# usb.net
KiCad netlist of a schematic drawn in Altium Designer
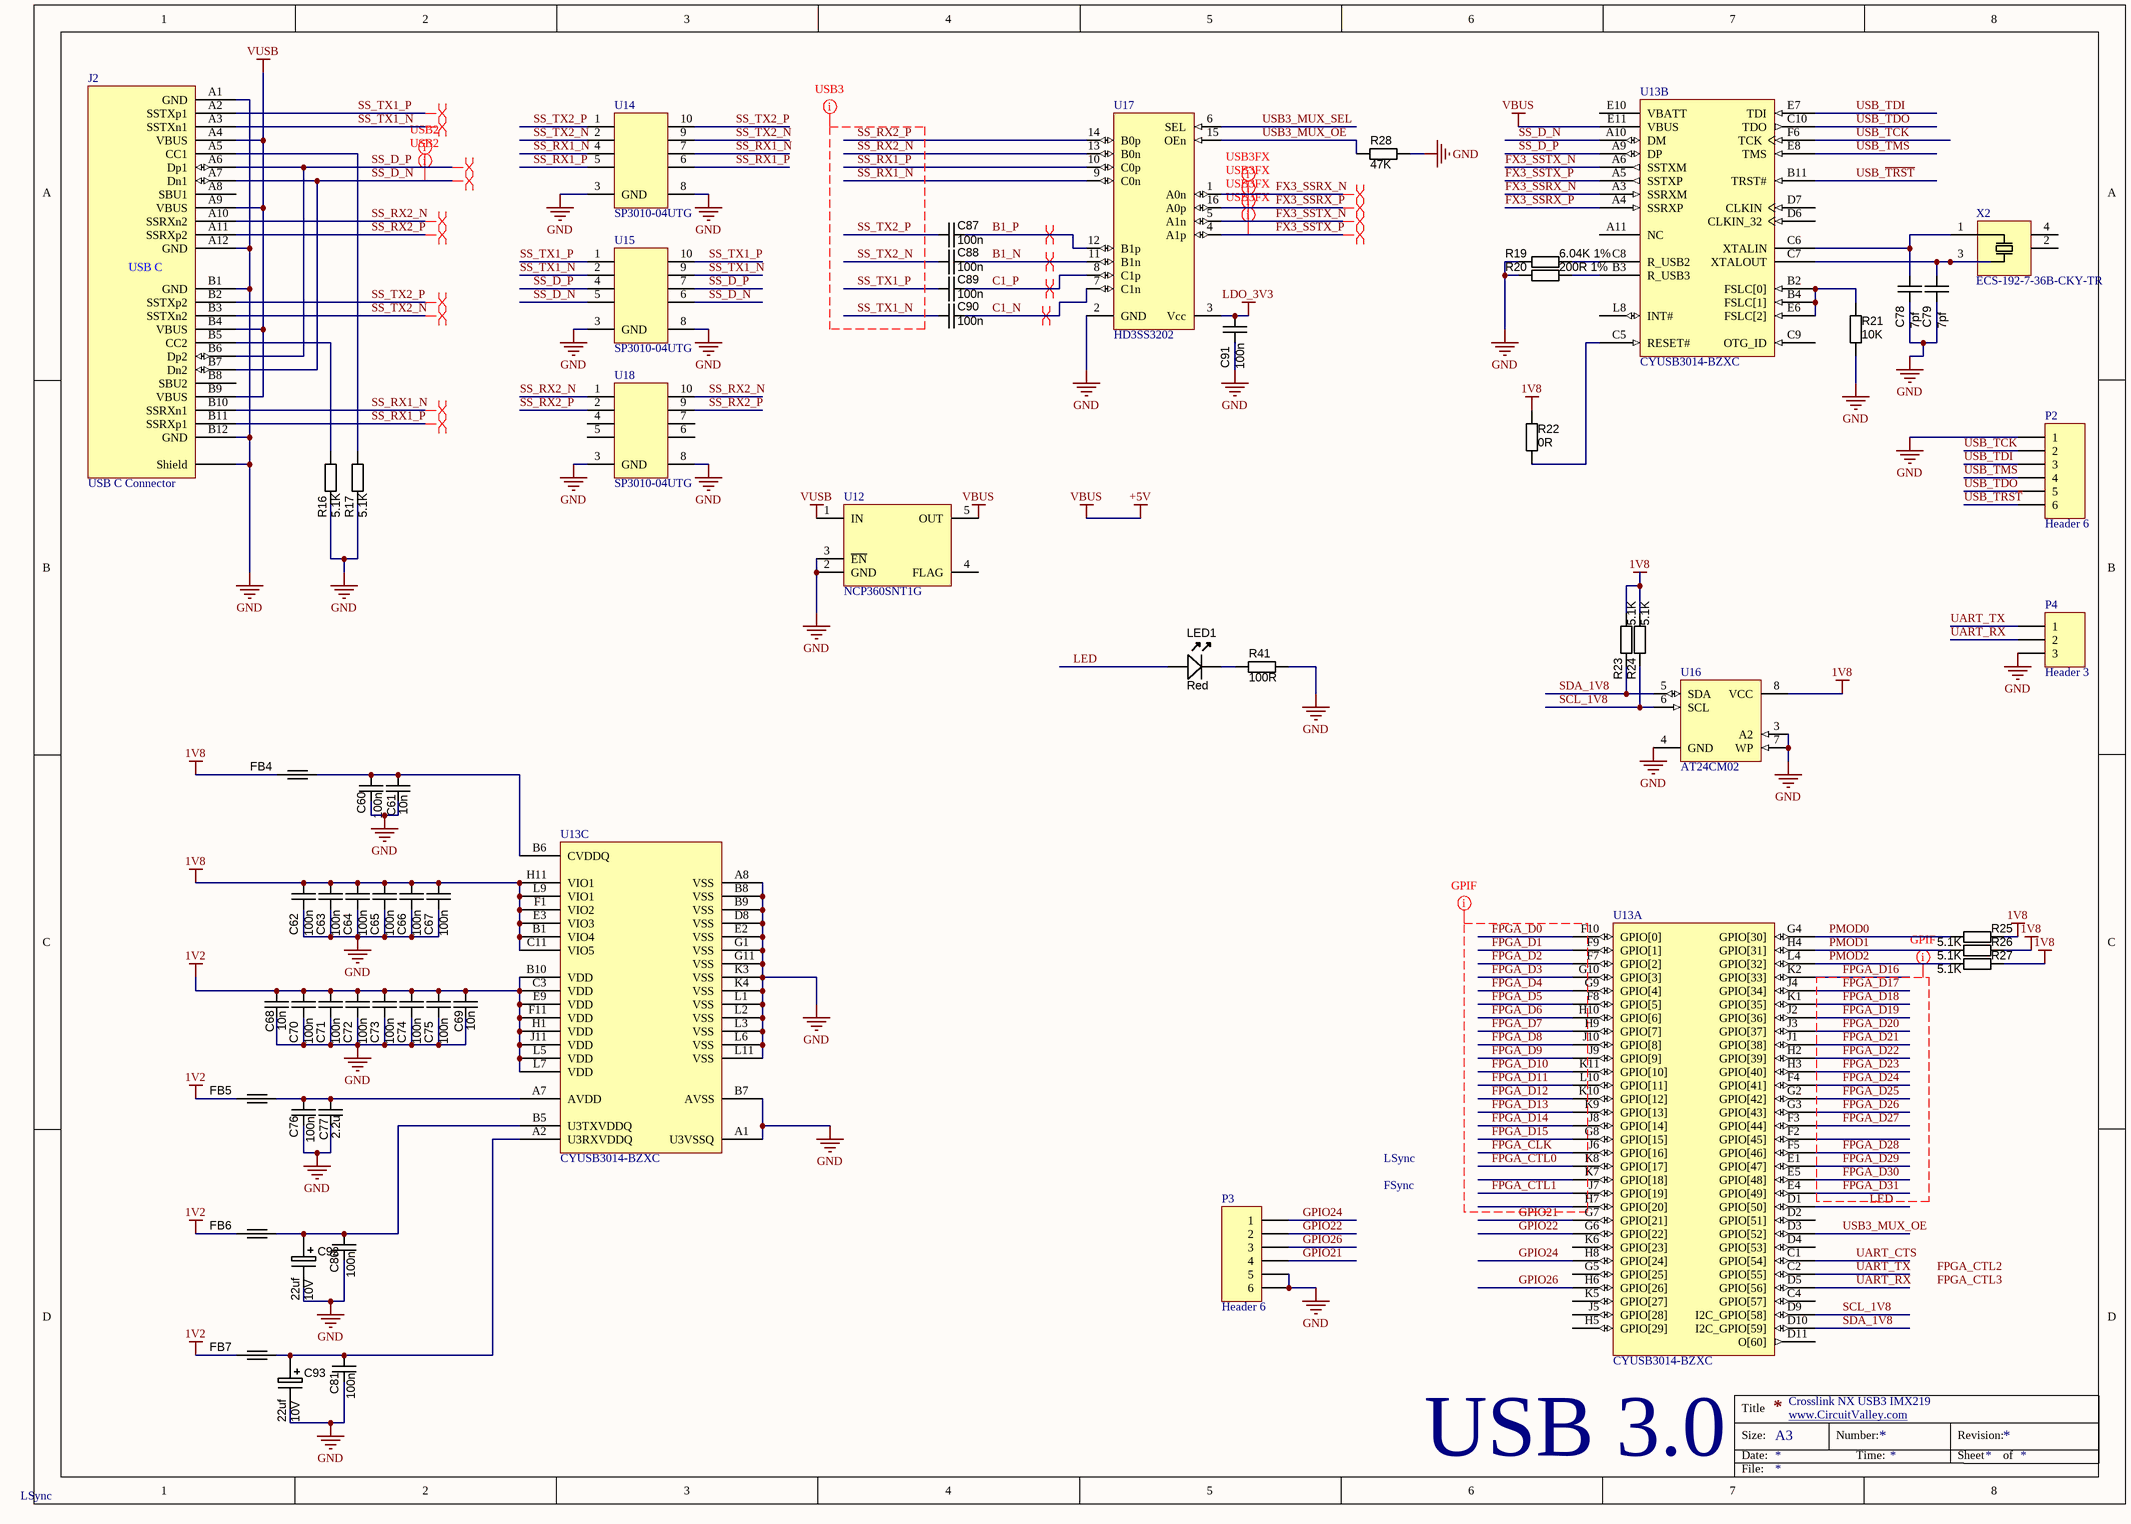
[diagram p0: usb.SchDoc]

(export (version "E")
  (design (tool "Eeschema 10.0.6"))
  (components
    (comp (ref "C60")
      (value "100n")
      (footprint "CAPC1608N")
      (description "Capacitor SMD Cer 10pF 5% 50V NP0 0603")
      (fields (field (name "TOLERANCE") "±5%") (field (name "PART") "C0603X104K5RAC"))
      (libsource (lib "PBL - Capacitors") (part "CAPC_10p_0603_NP0_1%_50V"))
    )
    (comp (ref "C61")
      (value "10n")
      (footprint "CAPC1608N")
      (description "Capacitor SMD Cer 10pF 5% 50V NP0 0603")
      (fields (field (name "TOLERANCE") "±5%") (field (name "PART") "C0603X104K5RAC"))
      (libsource (lib "PBL - Capacitors") (part "CAPC_10p_0603_NP0_1%_50V"))
    )
    (comp (ref "C62")
      (value "100n")
      (footprint "CAPC1608N")
      (description "Capacitor SMD Cer 10pF 5% 50V NP0 0603")
      (fields (field (name "TOLERANCE") "±5%") (field (name "PART") "C0603X104K5RAC"))
      (libsource (lib "PBL - Capacitors") (part "CAPC_10p_0603_NP0_1%_50V"))
    )
    (comp (ref "C63")
      (value "100n")
      (footprint "CAPC1608N")
      (description "Capacitor SMD Cer 10pF 5% 50V NP0 0603")
      (fields (field (name "TOLERANCE") "±5%") (field (name "PART") "C0603X104K5RAC"))
      (libsource (lib "PBL - Capacitors") (part "CAPC_10p_0603_NP0_1%_50V"))
    )
    (comp (ref "C64")
      (value "100n")
      (footprint "CAPC1608N")
      (description "Capacitor SMD Cer 10pF 5% 50V NP0 0603")
      (fields (field (name "TOLERANCE") "±5%") (field (name "PART") "C0603X104K5RAC"))
      (libsource (lib "PBL - Capacitors") (part "CAPC_10p_0603_NP0_1%_50V"))
    )
    (comp (ref "C65")
      (value "100n")
      (footprint "CAPC1608N")
      (description "Capacitor SMD Cer 10pF 5% 50V NP0 0603")
      (fields (field (name "TOLERANCE") "±5%") (field (name "PART") "C0603X104K5RAC"))
      (libsource (lib "PBL - Capacitors") (part "CAPC_10p_0603_NP0_1%_50V"))
    )
    (comp (ref "C66")
      (value "100n")
      (footprint "CAPC1608N")
      (description "Capacitor SMD Cer 10pF 5% 50V NP0 0603")
      (fields (field (name "TOLERANCE") "±5%") (field (name "PART") "C0603X104K5RAC"))
      (libsource (lib "PBL - Capacitors") (part "CAPC_10p_0603_NP0_1%_50V"))
    )
    (comp (ref "C67")
      (value "100n")
      (footprint "CAPC1608N")
      (description "Capacitor SMD Cer 10pF 5% 50V NP0 0603")
      (fields (field (name "TOLERANCE") "±5%") (field (name "PART") "C0603X104K5RAC"))
      (libsource (lib "PBL - Capacitors") (part "CAPC_10p_0603_NP0_1%_50V"))
    )
    (comp (ref "C68")
      (value "10n")
      (footprint "CAPC1608N")
      (description "Capacitor SMD Cer 10pF 5% 50V NP0 0603")
      (fields (field (name "TOLERANCE") "±5%") (field (name "PART") "C0603X104K5RAC"))
      (libsource (lib "PBL - Capacitors") (part "CAPC_10p_0603_NP0_1%_50V"))
    )
    (comp (ref "C69")
      (value "10n")
      (footprint "CAPC1608N")
      (description "Capacitor SMD Cer 10pF 5% 50V NP0 0603")
      (fields (field (name "TOLERANCE") "±5%") (field (name "PART") "C0603X104K5RAC"))
      (libsource (lib "PBL - Capacitors") (part "CAPC_10p_0603_NP0_1%_50V"))
    )
    (comp (ref "C70")
      (value "100n")
      (footprint "CAPC1608N")
      (description "Capacitor SMD Cer 10pF 5% 50V NP0 0603")
      (fields (field (name "TOLERANCE") "±5%") (field (name "PART") "C0603X104K5RAC"))
      (libsource (lib "PBL - Capacitors") (part "CAPC_10p_0603_NP0_1%_50V"))
    )
    (comp (ref "C71")
      (value "100n")
      (footprint "CAPC1608N")
      (description "Capacitor SMD Cer 10pF 5% 50V NP0 0603")
      (fields (field (name "TOLERANCE") "±5%") (field (name "PART") "C0603X104K5RAC"))
      (libsource (lib "PBL - Capacitors") (part "CAPC_10p_0603_NP0_1%_50V"))
    )
    (comp (ref "C72")
      (value "100n")
      (footprint "CAPC1608N")
      (description "Capacitor SMD Cer 10pF 5% 50V NP0 0603")
      (fields (field (name "TOLERANCE") "±5%") (field (name "PART") "C0603X104K5RAC"))
      (libsource (lib "PBL - Capacitors") (part "CAPC_10p_0603_NP0_1%_50V"))
    )
    (comp (ref "C73")
      (value "100n")
      (footprint "CAPC1608N")
      (description "Capacitor SMD Cer 10pF 5% 50V NP0 0603")
      (fields (field (name "TOLERANCE") "±5%") (field (name "PART") "C0603X104K5RAC"))
      (libsource (lib "PBL - Capacitors") (part "CAPC_10p_0603_NP0_1%_50V"))
    )
    (comp (ref "C74")
      (value "100n")
      (footprint "CAPC1608N")
      (description "Capacitor SMD Cer 10pF 5% 50V NP0 0603")
      (fields (field (name "TOLERANCE") "±5%") (field (name "PART") "C0603X104K5RAC"))
      (libsource (lib "PBL - Capacitors") (part "CAPC_10p_0603_NP0_1%_50V"))
    )
    (comp (ref "C75")
      (value "100n")
      (footprint "CAPC1608N")
      (description "Capacitor SMD Cer 10pF 5% 50V NP0 0603")
      (fields (field (name "TOLERANCE") "±5%") (field (name "PART") "C0603X104K5RAC"))
      (libsource (lib "PBL - Capacitors") (part "CAPC_10p_0603_NP0_1%_50V"))
    )
    (comp (ref "C76")
      (value "100n")
      (footprint "CAPC1608N")
      (description "Capacitor SMD Cer 10pF 5% 50V NP0 0603")
      (fields (field (name "TOLERANCE") "±5%") (field (name "PART") "C0603X104K5RAC"))
      (libsource (lib "PBL - Capacitors") (part "CAPC_10p_0603_NP0_1%_50V"))
    )
    (comp (ref "C77")
      (value "2.2u")
      (footprint "CAPC1608N")
      (description "Capacitor SMD Cer 10pF 5% 50V NP0 0603")
      (fields (field (name "TOLERANCE") "±5%") (field (name "PART") "C0603X104K5RAC"))
      (libsource (lib "PBL - Capacitors") (part "CAPC_10p_0603_NP0_1%_50V"))
    )
    (comp (ref "C78")
      (value "7pf")
      (footprint "CAPC1608N")
      (description "Capacitor SMD Cer 10pF 5% 50V NP0 0603")
      (fields (field (name "TOLERANCE") "±5%") (field (name "PART") "C0603X104K5RAC"))
      (libsource (lib "PBL - Capacitors") (part "CAPC_10p_0603_NP0_1%_50V"))
    )
    (comp (ref "C79")
      (value "7pf")
      (footprint "CAPC1608N")
      (description "Capacitor SMD Cer 10pF 5% 50V NP0 0603")
      (fields (field (name "TOLERANCE") "±5%") (field (name "PART") "C0603X104K5RAC"))
      (libsource (lib "PBL - Capacitors") (part "CAPC_10p_0603_NP0_1%_50V"))
    )
    (comp (ref "C80")
      (value "100n")
      (footprint "CAPC1608N")
      (description "Capacitor SMD Cer 10pF 5% 50V NP0 0603")
      (fields (field (name "TOLERANCE") "±5%") (field (name "PART") "C0603X104K5RAC"))
      (libsource (lib "PBL - Capacitors") (part "CAPC_10p_0603_NP0_1%_50V"))
    )
    (comp (ref "C81")
      (value "100n")
      (footprint "CAPC1608N")
      (description "Capacitor SMD Cer 10pF 5% 50V NP0 0603")
      (fields (field (name "TOLERANCE") "±5%") (field (name "PART") "C0603X104K5RAC"))
      (libsource (lib "PBL - Capacitors") (part "CAPC_10p_0603_NP0_1%_50V"))
    )
    (comp (ref "C87")
      (value "100n")
      (footprint "CAPC1005N")
      (description "Capacitor SMD Cer 10nF 10% 16V X7R 0402")
      (fields (field (name "TOLERANCE") "±10%"))
      (libsource (lib "PBL - Capacitors") (part "CAPC_10n_0402_16V_10%"))
    )
    (comp (ref "C88")
      (value "100n")
      (footprint "CAPC1005N")
      (description "Capacitor SMD Cer 10nF 10% 16V X7R 0402")
      (fields (field (name "TOLERANCE") "±10%"))
      (libsource (lib "PBL - Capacitors") (part "CAPC_10n_0402_16V_10%"))
    )
    (comp (ref "C89")
      (value "100n")
      (footprint "CAPC1005N")
      (description "Capacitor SMD Cer 10nF 10% 16V X7R 0402")
      (fields (field (name "TOLERANCE") "±10%"))
      (libsource (lib "PBL - Capacitors") (part "CAPC_10n_0402_16V_10%"))
    )
    (comp (ref "C90")
      (value "100n")
      (footprint "CAPC1005N")
      (description "Capacitor SMD Cer 10nF 10% 16V X7R 0402")
      (fields (field (name "TOLERANCE") "±10%"))
      (libsource (lib "PBL - Capacitors") (part "CAPC_10n_0402_16V_10%"))
    )
    (comp (ref "C91")
      (value "100n")
      (footprint "CAPC1608N")
      (description "Capacitor SMD Cer 10pF 5% 50V NP0 0603")
      (fields (field (name "TOLERANCE") "±5%") (field (name "PART") "C0603X104K5RAC"))
      (libsource (lib "PBL - Capacitors") (part "CAPC_10p_0603_NP0_1%_50V"))
    )
    (comp (ref "C92")
      (value "22uf")
      (footprint "CAPMP3528X210N")
      (description "Capacitor SMD Tantalum 47uF 20% 6.3V 1210")
      (fields (field (name "TOLERANCE") "±20%") (field (name "RATINGS") "10V"))
      (libsource (lib "PBL - Capacitors") (part "CAPT_47u_1210_6V3"))
    )
    (comp (ref "C93")
      (value "22uf")
      (footprint "CAPMP3528X210N")
      (description "Capacitor SMD Tantalum 47uF 20% 6.3V 1210")
      (fields (field (name "TOLERANCE") "±20%") (field (name "RATINGS") "10V"))
      (libsource (lib "PBL - Capacitors") (part "CAPT_47u_1210_6V3"))
    )
    (comp (ref "FB4")
      (value "~")
      (footprint "FBC2012N")
      (description "Ferrite bead 2.2K Ohm at 100 MHz 200mA 0805 SMD")
      (libsource (lib "PBL - Inductors") (part "FERRITE_0805"))
    )
    (comp (ref "FB5")
      (value "~")
      (footprint "FBC2012N")
      (description "Ferrite bead 2.2K Ohm at 100 MHz 200mA 0805 SMD")
      (libsource (lib "PBL - Inductors") (part "FERRITE_0805"))
    )
    (comp (ref "FB6")
      (value "~")
      (footprint "FBC2012N")
      (description "Ferrite bead 2.2K Ohm at 100 MHz 200mA 0805 SMD")
      (libsource (lib "PBL - Inductors") (part "FERRITE_0805"))
    )
    (comp (ref "FB7")
      (value "~")
      (footprint "FBC2012N")
      (description "Ferrite bead 2.2K Ohm at 100 MHz 200mA 0805 SMD")
      (libsource (lib "PBL - Inductors") (part "FERRITE_0805"))
    )
    (comp (ref "J2")
      (value "USB C Connector")
      (footprint "10137062-00021LF")
      (description "USB C connector")
      (libsource (lib "cvlib") (part "USB_C"))
    )
    (comp (ref "LED1")
      (value "Red")
      (footprint "LED-0603-RED")
      (description "LED 0603 SMD Hyper Red 630nm 220mcd 20mA")
      (libsource (lib "PBL - Light Sources") (part "LED_SMD_Red_0603_220mcd"))
    )
    (comp (ref "P2")
      (value "Header 6")
      (footprint "SMD_Solder_points_1.27")
      (description "Header, 6-Pin")
      (fields (field (name "PUBLISHER") "Altium Limited"))
      (libsource (lib "") (part "Header 6_1"))
    )
    (comp (ref "P3")
      (value "Header 6")
      (footprint "SMD_Solder_points_1.27")
      (description "Header, 6-Pin")
      (fields (field (name "PUBLISHER") "Altium Limited"))
      (libsource (lib "Miscellaneous Connectors") (part "Header 6"))
    )
    (comp (ref "P4")
      (value "Header 3")
      (footprint "SMD_3Solder_points_1.27")
      (description "Header, 3-Pin")
      (fields (field (name "PUBLISHER") "Altium Limited"))
      (libsource (lib "Miscellaneous Connectors") (part "Header 3"))
    )
    (comp (ref "R16")
      (value "5.1K")
      (footprint "RESC1608N_ZERO")
      (description "Resistor SMD chip 0.0 Ohm 0.1W 0603")
      (fields (field (name "TOLERANCE") "±5%") (field (name "Comment") "Thick Film"))
      (libsource (lib "") (part "RES_0R_0603_1"))
    )
    (comp (ref "R17")
      (value "5.1K")
      (footprint "RESC1608N_ZERO")
      (description "Resistor SMD chip 0.0 Ohm 0.1W 0603")
      (fields (field (name "TOLERANCE") "±5%") (field (name "Comment") "Thick Film"))
      (libsource (lib "") (part "RES_0R_0603_1"))
    )
    (comp (ref "R19")
      (value "6.04K 1%")
      (footprint "RESC1608N_ZERO")
      (description "Resistor SMD chip 0.0 Ohm 0.1W 0603")
      (fields (field (name "TOLERANCE") "±5%") (field (name "Comment") "Thick Film"))
      (libsource (lib "PBL - Resistors") (part "RES_0R_0603"))
    )
    (comp (ref "R20")
      (value "200R 1%")
      (footprint "RESC1608N_ZERO")
      (description "Resistor SMD chip 0.0 Ohm 0.1W 0603")
      (fields (field (name "TOLERANCE") "±5%") (field (name "Comment") "Thick Film"))
      (libsource (lib "PBL - Resistors") (part "RES_0R_0603"))
    )
    (comp (ref "R21")
      (value "10K")
      (footprint "RESC1608N_ZERO")
      (description "Resistor SMD chip 0.0 Ohm 0.1W 0603")
      (fields (field (name "TOLERANCE") "±5%") (field (name "Comment") "Thick Film"))
      (libsource (lib "") (part "RES_0R_0603_1"))
    )
    (comp (ref "R22")
      (value "0R")
      (footprint "RESC1608N_ZERO")
      (description "Resistor SMD chip 0.0 Ohm 0.1W 0603")
      (fields (field (name "TOLERANCE") "±5%") (field (name "Comment") "Thick Film"))
      (libsource (lib "") (part "RES_0R_0603_3"))
    )
    (comp (ref "R23")
      (value "5.1K")
      (footprint "RESC1608N_ZERO")
      (description "Resistor SMD chip 0.0 Ohm 0.1W 0603")
      (fields (field (name "TOLERANCE") "±5%") (field (name "Comment") "Thick Film"))
      (libsource (lib "") (part "RES_0R_0603_3"))
    )
    (comp (ref "R24")
      (value "5.1K")
      (footprint "RESC1608N_ZERO")
      (description "Resistor SMD chip 0.0 Ohm 0.1W 0603")
      (fields (field (name "TOLERANCE") "±5%") (field (name "Comment") "Thick Film"))
      (libsource (lib "") (part "RES_0R_0603_1"))
    )
    (comp (ref "R25")
      (value "5.1K")
      (footprint "RESC1608N_ZERO")
      (description "Resistor SMD chip 0.0 Ohm 0.1W 0603")
      (fields (field (name "TOLERANCE") "±5%") (field (name "Comment") "Thick Film"))
      (libsource (lib "") (part "RES_0R_0603_2"))
    )
    (comp (ref "R26")
      (value "5.1K")
      (footprint "RESC1608N_ZERO")
      (description "Resistor SMD chip 0.0 Ohm 0.1W 0603")
      (fields (field (name "TOLERANCE") "±5%") (field (name "Comment") "Thick Film"))
      (libsource (lib "") (part "RES_0R_0603_2"))
    )
    (comp (ref "R27")
      (value "5.1K")
      (footprint "RESC1608N_ZERO")
      (description "Resistor SMD chip 0.0 Ohm 0.1W 0603")
      (fields (field (name "TOLERANCE") "±5%") (field (name "Comment") "Thick Film"))
      (libsource (lib "") (part "RES_0R_0603_2"))
    )
    (comp (ref "R28")
      (value "47K")
      (footprint "RESC1608N_ZERO")
      (description "Resistor SMD chip 0.0 Ohm 0.1W 0603")
      (fields (field (name "TOLERANCE") "±5%") (field (name "Comment") "Thick Film"))
      (libsource (lib "") (part "RES_0R_0603_2"))
    )
    (comp (ref "R41")
      (value "100R")
      (footprint "RESC1608N_ZERO")
      (description "Resistor SMD chip 0.0 Ohm 0.1W 0603")
      (fields (field (name "TOLERANCE") "±5%") (field (name "Comment") "Thick Film"))
      (libsource (lib "") (part "RES_0R_0603_2"))
    )
    (comp (ref "U12")
      (value "NCP360SNT1G")
      (footprint "SOT23-5")
      (description "USB Overvoltage Protection")
      (libsource (lib "cvlib") (part "NCP360SNT1G"))
    )
    (comp (ref "U13")
      (value "CYUSB3014-BZXC")
      (footprint "CYP-BZX121")
      (description "EZ-USB(R) FX3: SuperSpeed USB Controller, 512 KB, 60 I/Os, 0 to 70 degC, 121-Pin FBGA (BZX121)")
      (fields (field (name "MANUFACTURER") "Cypress"))
      (libsource (lib "") (part "CYUSB3014-BZXC_1"))
    )
    (comp (ref "U14")
      (value "SP3010-04UTG")
      (footprint "uDFN-10")
      (description "ESD Protection")
      (libsource (lib "cvlib") (part "SP3010-04UTG"))
    )
    (comp (ref "U15")
      (value "SP3010-04UTG")
      (footprint "uDFN-10")
      (description "ESD Protection")
      (libsource (lib "cvlib") (part "SP3010-04UTG"))
    )
    (comp (ref "U16")
      (value "AT24CM02")
      (footprint "SOIC8")
      (description "2Mbit I2C EEPROM")
      (libsource (lib "cvlib") (part "AT24CM02"))
    )
    (comp (ref "U17")
      (value "HD3SS3202")
      (footprint "UQFN-16")
      (description "USB 3.0 Mux")
      (libsource (lib "cvlib") (part "HD3SS3202"))
    )
    (comp (ref "U18")
      (value "SP3010-04UTG")
      (footprint "uDFN-10")
      (description "ESD Protection")
      (libsource (lib "cvlib") (part "SP3010-04UTG"))
    )
    (comp (ref "X2")
      (value "ECS-192-7-36B-CKY-TR")
      (footprint "Active Oscillator 2520")
      (description "Crystal Oscillator")
      (libsource (lib "cvlib") (part "Crystal"))
    )
  )
  (nets
    (net (code "1") (name "+5V") (class "Default")
      (node (ref "U12") (pin "5") (pinfunction "OUT_5") (pintype "power_in"))
      (node (ref "U13") (pin "E11") (pinfunction "VBUS_E11") (pintype "power_in"))
    )
    (net (code "2") (name "/B1_N") (class "Default")
      (node (ref "C88") (pin "2") (pintype "passive"))
      (node (ref "U17") (pin "11") (pinfunction "B1n_11") (pintype "bidirectional"))
    )
    (net (code "3") (name "/B1_P") (class "Default")
      (node (ref "C87") (pin "2") (pintype "passive"))
      (node (ref "U17") (pin "12") (pinfunction "B1p_12") (pintype "bidirectional"))
    )
    (net (code "4") (name "/C1_N") (class "Default")
      (node (ref "C90") (pin "2") (pintype "passive"))
      (node (ref "U17") (pin "7") (pinfunction "C1n_7") (pintype "bidirectional"))
    )
    (net (code "5") (name "/C1_P") (class "Default")
      (node (ref "C89") (pin "2") (pintype "passive"))
      (node (ref "U17") (pin "8") (pinfunction "C1p_8") (pintype "bidirectional"))
    )
    (net (code "6") (name "/FPGA_CLK") (class "Default")
      (node (ref "U13") (pin "J6") (pinfunction "GPIO[16]_J6") (pintype "bidirectional"))
    )
    (net (code "7") (name "/FPGA_CTL0") (class "Default")
      (node (ref "U13") (pin "K8") (pinfunction "GPIO[17]_K8") (pintype "bidirectional"))
    )
    (net (code "8") (name "/FPGA_CTL1") (class "Default")
      (node (ref "U13") (pin "J7") (pinfunction "GPIO[19]_J7") (pintype "bidirectional"))
    )
    (net (code "11") (name "/FPGA_D0") (class "Default")
      (node (ref "U13") (pin "F10") (pinfunction "GPIO[0]_F10") (pintype "bidirectional"))
    )
    (net (code "12") (name "/FPGA_D1") (class "Default")
      (node (ref "U13") (pin "F9") (pinfunction "GPIO[1]_F9") (pintype "bidirectional"))
    )
    (net (code "13") (name "/FPGA_D2") (class "Default")
      (node (ref "U13") (pin "F7") (pinfunction "GPIO[2]_F7") (pintype "bidirectional"))
    )
    (net (code "14") (name "/FPGA_D3") (class "Default")
      (node (ref "U13") (pin "G10") (pinfunction "GPIO[3]_G10") (pintype "bidirectional"))
    )
    (net (code "15") (name "/FPGA_D4") (class "Default")
      (node (ref "U13") (pin "G9") (pinfunction "GPIO[4]_G9") (pintype "bidirectional"))
    )
    (net (code "16") (name "/FPGA_D5") (class "Default")
      (node (ref "U13") (pin "F8") (pinfunction "GPIO[5]_F8") (pintype "bidirectional"))
    )
    (net (code "17") (name "/FPGA_D6") (class "Default")
      (node (ref "U13") (pin "H10") (pinfunction "GPIO[6]_H10") (pintype "bidirectional"))
    )
    (net (code "18") (name "/FPGA_D7") (class "Default")
      (node (ref "U13") (pin "H9") (pinfunction "GPIO[7]_H9") (pintype "bidirectional"))
    )
    (net (code "19") (name "/FPGA_D8") (class "Default")
      (node (ref "U13") (pin "J10") (pinfunction "GPIO[8]_J10") (pintype "bidirectional"))
    )
    (net (code "20") (name "/FPGA_D9") (class "Default")
      (node (ref "U13") (pin "J9") (pinfunction "GPIO[9]_J9") (pintype "bidirectional"))
    )
    (net (code "21") (name "/FPGA_D10") (class "Default")
      (node (ref "U13") (pin "K11") (pinfunction "GPIO[10]_K11") (pintype "bidirectional"))
    )
    (net (code "22") (name "/FPGA_D11") (class "Default")
      (node (ref "U13") (pin "L10") (pinfunction "GPIO[11]_L10") (pintype "bidirectional"))
    )
    (net (code "23") (name "/FPGA_D12") (class "Default")
      (node (ref "U13") (pin "K10") (pinfunction "GPIO[12]_K10") (pintype "bidirectional"))
    )
    (net (code "24") (name "/FPGA_D13") (class "Default")
      (node (ref "U13") (pin "K9") (pinfunction "GPIO[13]_K9") (pintype "bidirectional"))
    )
    (net (code "25") (name "/FPGA_D14") (class "Default")
      (node (ref "U13") (pin "J8") (pinfunction "GPIO[14]_J8") (pintype "bidirectional"))
    )
    (net (code "26") (name "/FPGA_D15") (class "Default")
      (node (ref "U13") (pin "G8") (pinfunction "GPIO[15]_G8") (pintype "bidirectional"))
    )
    (net (code "27") (name "/FPGA_D16") (class "Default")
      (node (ref "U13") (pin "K2") (pinfunction "GPIO[33]_K2") (pintype "bidirectional"))
    )
    (net (code "28") (name "/FPGA_D17") (class "Default")
      (node (ref "U13") (pin "J4") (pinfunction "GPIO[34]_J4") (pintype "bidirectional"))
    )
    (net (code "29") (name "/FPGA_D18") (class "Default")
      (node (ref "U13") (pin "K1") (pinfunction "GPIO[35]_K1") (pintype "bidirectional"))
    )
    (net (code "30") (name "/FPGA_D19") (class "Default")
      (node (ref "U13") (pin "J2") (pinfunction "GPIO[36]_J2") (pintype "bidirectional"))
    )
    (net (code "31") (name "/FPGA_D20") (class "Default")
      (node (ref "U13") (pin "J3") (pinfunction "GPIO[37]_J3") (pintype "bidirectional"))
    )
    (net (code "32") (name "/FPGA_D21") (class "Default")
      (node (ref "U13") (pin "J1") (pinfunction "GPIO[38]_J1") (pintype "bidirectional"))
    )
    (net (code "33") (name "/FPGA_D22") (class "Default")
      (node (ref "U13") (pin "H2") (pinfunction "GPIO[39]_H2") (pintype "bidirectional"))
    )
    (net (code "34") (name "/FPGA_D23") (class "Default")
      (node (ref "U13") (pin "H3") (pinfunction "GPIO[40]_H3") (pintype "bidirectional"))
    )
    (net (code "35") (name "/FPGA_D24") (class "Default")
      (node (ref "U13") (pin "F4") (pinfunction "GPIO[41]_F4") (pintype "bidirectional"))
    )
    (net (code "36") (name "/FPGA_D25") (class "Default")
      (node (ref "U13") (pin "G2") (pinfunction "GPIO[42]_G2") (pintype "bidirectional"))
    )
    (net (code "37") (name "/FPGA_D26") (class "Default")
      (node (ref "U13") (pin "G3") (pinfunction "GPIO[43]_G3") (pintype "bidirectional"))
    )
    (net (code "38") (name "/FPGA_D27") (class "Default")
      (node (ref "U13") (pin "F3") (pinfunction "GPIO[44]_F3") (pintype "bidirectional"))
    )
    (net (code "39") (name "/FPGA_D28") (class "Default")
      (node (ref "U13") (pin "F5") (pinfunction "GPIO[46]_F5") (pintype "bidirectional"))
    )
    (net (code "40") (name "/FPGA_D29") (class "Default")
      (node (ref "U13") (pin "E1") (pinfunction "GPIO[47]_E1") (pintype "bidirectional"))
    )
    (net (code "41") (name "/FPGA_D30") (class "Default")
      (node (ref "U13") (pin "E5") (pinfunction "GPIO[48]_E5") (pintype "bidirectional"))
    )
    (net (code "42") (name "/FPGA_D31") (class "Default")
      (node (ref "U13") (pin "E4") (pinfunction "GPIO[49]_E4") (pintype "bidirectional"))
    )
    (net (code "43") (name "/FX3_SSRX_N") (class "Default")
      (node (ref "U13") (pin "A3") (pinfunction "SSRXM_A3") (pintype "input"))
      (node (ref "U17") (pin "1") (pinfunction "A0n_1") (pintype "bidirectional"))
    )
    (net (code "44") (name "/FX3_SSRX_P") (class "Default")
      (node (ref "U13") (pin "A4") (pinfunction "SSRXP_A4") (pintype "input"))
      (node (ref "U17") (pin "16") (pinfunction "A0p_16") (pintype "bidirectional"))
    )
    (net (code "45") (name "/FX3_SSTX_N") (class "Default")
      (node (ref "U13") (pin "A6") (pinfunction "SSTXM_A6") (pintype "output"))
      (node (ref "U17") (pin "5") (pinfunction "A1n_5") (pintype "bidirectional"))
    )
    (net (code "46") (name "/FX3_SSTX_P") (class "Default")
      (node (ref "U13") (pin "A5") (pinfunction "SSTXP_A5") (pintype "output"))
      (node (ref "U17") (pin "4") (pinfunction "A1p_4") (pintype "bidirectional"))
    )
    (net (code "47") (name "/GPIO21") (class "Default")
      (node (ref "P3") (pin "4") (pinfunction "4_4") (pintype "passive"))
      (node (ref "U13") (pin "G7") (pinfunction "GPIO[21]_G7") (pintype "bidirectional"))
    )
    (net (code "48") (name "/GPIO22") (class "Default")
      (node (ref "P3") (pin "2") (pinfunction "2_2") (pintype "passive"))
      (node (ref "U13") (pin "G6") (pinfunction "GPIO[22]_G6") (pintype "bidirectional"))
    )
    (net (code "49") (name "/GPIO24") (class "Default")
      (node (ref "P3") (pin "1") (pinfunction "1_1") (pintype "passive"))
      (node (ref "U13") (pin "H8") (pinfunction "GPIO[24]_H8") (pintype "bidirectional"))
    )
    (net (code "50") (name "/GPIO26") (class "Default")
      (node (ref "P3") (pin "3") (pinfunction "3_3") (pintype "passive"))
      (node (ref "U13") (pin "H6") (pinfunction "GPIO[26]_H6") (pintype "bidirectional"))
    )
    (net (code "51") (name "/LED") (class "Default")
      (node (ref "LED1") (pin "A") (pinfunction "A_A") (pintype "passive"))
      (node (ref "U13") (pin "D1") (pinfunction "GPIO[50]_D1") (pintype "bidirectional"))
    )
    (net (code "52") (name "/PMOD0") (class "Default")
      (node (ref "R25") (pin "1") (pinfunction "1_1") (pintype "passive"))
      (node (ref "U13") (pin "G4") (pinfunction "GPIO[30]_G4") (pintype "bidirectional"))
    )
    (net (code "53") (name "/PMOD1") (class "Default")
      (node (ref "R26") (pin "1") (pinfunction "1_1") (pintype "passive"))
      (node (ref "U13") (pin "H4") (pinfunction "GPIO[31]_H4") (pintype "bidirectional"))
    )
    (net (code "54") (name "/PMOD2") (class "Default")
      (node (ref "R27") (pin "1") (pinfunction "1_1") (pintype "passive"))
      (node (ref "U13") (pin "L4") (pinfunction "GPIO[32]_L4") (pintype "bidirectional"))
    )
    (net (code "55") (name "/SCL_1V8") (class "Default")
      (node (ref "R24") (pin "2") (pinfunction "2_2") (pintype "passive"))
      (node (ref "U13") (pin "D9") (pinfunction "I2C_GPIO[58]_D9") (pintype "bidirectional"))
      (node (ref "U16") (pin "6") (pinfunction "SCL_6") (pintype "input"))
    )
    (net (code "56") (name "/SDA_1V8") (class "Default")
      (node (ref "R23") (pin "1") (pinfunction "1_1") (pintype "passive"))
      (node (ref "U13") (pin "D10") (pinfunction "I2C_GPIO[59]_D10") (pintype "bidirectional"))
      (node (ref "U16") (pin "5") (pinfunction "SDA_5") (pintype "bidirectional"))
    )
    (net (code "57") (name "/SS_D_N") (class "Default")
      (node (ref "J2") (pin "A7") (pinfunction "Dn1_A7") (pintype "bidirectional"))
      (node (ref "J2") (pin "B7") (pinfunction "Dn2_B7") (pintype "bidirectional"))
      (node (ref "U13") (pin "A10") (pinfunction "DM_A10") (pintype "bidirectional"))
      (node (ref "U15") (pin "5") (pintype "passive"))
      (node (ref "U15") (pin "6") (pintype "passive"))
    )
    (net (code "58") (name "/SS_D_P") (class "Default")
      (node (ref "J2") (pin "A6") (pinfunction "Dp1_A6") (pintype "bidirectional"))
      (node (ref "J2") (pin "B6") (pinfunction "Dp2_B6") (pintype "bidirectional"))
      (node (ref "U13") (pin "A9") (pinfunction "DP_A9") (pintype "bidirectional"))
      (node (ref "U15") (pin "4") (pintype "passive"))
      (node (ref "U15") (pin "7") (pintype "passive"))
    )
    (net (code "59") (name "/SS_RX1_N") (class "Default")
      (node (ref "J2") (pin "B10") (pinfunction "SSRXn1_B10") (pintype "passive"))
      (node (ref "U14") (pin "4") (pintype "passive"))
      (node (ref "U14") (pin "7") (pintype "passive"))
      (node (ref "U17") (pin "9") (pinfunction "C0n_9") (pintype "bidirectional"))
    )
    (net (code "60") (name "/SS_RX1_P") (class "Default")
      (node (ref "J2") (pin "B11") (pinfunction "SSRXp1_B11") (pintype "passive"))
      (node (ref "U14") (pin "5") (pintype "passive"))
      (node (ref "U14") (pin "6") (pintype "passive"))
      (node (ref "U17") (pin "10") (pinfunction "C0p_10") (pintype "bidirectional"))
    )
    (net (code "61") (name "/SS_RX2_N") (class "Default")
      (node (ref "J2") (pin "A10") (pinfunction "SSRXn2_A10") (pintype "passive"))
      (node (ref "U17") (pin "13") (pinfunction "B0n_13") (pintype "bidirectional"))
      (node (ref "U18") (pin "1") (pintype "passive"))
      (node (ref "U18") (pin "10") (pintype "passive"))
    )
    (net (code "62") (name "/SS_RX2_P") (class "Default")
      (node (ref "J2") (pin "A11") (pinfunction "SSRXp2_A11") (pintype "passive"))
      (node (ref "U17") (pin "14") (pinfunction "B0p_14") (pintype "bidirectional"))
      (node (ref "U18") (pin "2") (pintype "passive"))
      (node (ref "U18") (pin "9") (pintype "passive"))
    )
    (net (code "63") (name "/SS_TX1_N") (class "Default")
      (node (ref "C90") (pin "1") (pintype "passive"))
      (node (ref "J2") (pin "A3") (pinfunction "SSTXn1_A3") (pintype "passive"))
      (node (ref "U15") (pin "2") (pintype "passive"))
      (node (ref "U15") (pin "9") (pintype "passive"))
    )
    (net (code "64") (name "/SS_TX1_P") (class "Default")
      (node (ref "C89") (pin "1") (pintype "passive"))
      (node (ref "J2") (pin "A2") (pinfunction "SSTXp1_A2") (pintype "passive"))
      (node (ref "U15") (pin "1") (pintype "passive"))
      (node (ref "U15") (pin "10") (pintype "passive"))
    )
    (net (code "65") (name "/SS_TX2_N") (class "Default")
      (node (ref "C88") (pin "1") (pintype "passive"))
      (node (ref "J2") (pin "B3") (pinfunction "SSTXn2_B3") (pintype "passive"))
      (node (ref "U14") (pin "2") (pintype "passive"))
      (node (ref "U14") (pin "9") (pintype "passive"))
    )
    (net (code "66") (name "/SS_TX2_P") (class "Default")
      (node (ref "C87") (pin "1") (pintype "passive"))
      (node (ref "J2") (pin "B2") (pinfunction "SSTXp2_B2") (pintype "passive"))
      (node (ref "U14") (pin "1") (pintype "passive"))
      (node (ref "U14") (pin "10") (pintype "passive"))
    )
    (net (code "67") (name "/UART_CTS") (class "Default")
      (node (ref "U13") (pin "C1") (pinfunction "GPIO[54]_C1") (pintype "bidirectional"))
    )
    (net (code "68") (name "/UART_RX") (class "Default")
      (node (ref "P4") (pin "2") (pinfunction "2_2") (pintype "passive"))
      (node (ref "U13") (pin "D5") (pinfunction "GPIO[56]_D5") (pintype "bidirectional"))
    )
    (net (code "69") (name "/UART_TX") (class "Default")
      (node (ref "P4") (pin "1") (pinfunction "1_1") (pintype "passive"))
      (node (ref "U13") (pin "C2") (pinfunction "GPIO[55]_C2") (pintype "bidirectional"))
    )
    (net (code "70") (name "/USB3_MUX_OE") (class "Default")
      (node (ref "R28") (pin "1") (pinfunction "1_1") (pintype "passive"))
      (node (ref "U13") (pin "D3") (pinfunction "GPIO[52]_D3") (pintype "bidirectional"))
      (node (ref "U17") (pin "15") (pinfunction "OEn_15") (pintype "input"))
    )
    (net (code "71") (name "/USB3_MUX_SEL") (class "Default")
      (node (ref "U17") (pin "6") (pinfunction "SEL_6") (pintype "input"))
    )
    (net (code "72") (name "/USB_TCK") (class "Default")
      (node (ref "P2") (pin "2") (pinfunction "2_2") (pintype "passive"))
      (node (ref "U13") (pin "F6") (pinfunction "TCK_F6") (pintype "input"))
    )
    (net (code "73") (name "/USB_TDI") (class "Default")
      (node (ref "P2") (pin "3") (pinfunction "3_3") (pintype "passive"))
      (node (ref "U13") (pin "E7") (pinfunction "TDI_E7") (pintype "input"))
    )
    (net (code "74") (name "/USB_TDO") (class "Default")
      (node (ref "P2") (pin "5") (pinfunction "5_5") (pintype "passive"))
      (node (ref "U13") (pin "C10") (pinfunction "TDO_C10") (pintype "output"))
    )
    (net (code "75") (name "/USB_TMS") (class "Default")
      (node (ref "P2") (pin "4") (pinfunction "4_4") (pintype "passive"))
      (node (ref "U13") (pin "E8") (pinfunction "TMS_E8") (pintype "input"))
    )
    (net (code "76") (name "/USB_~{TRST}") (class "Default")
      (node (ref "P2") (pin "6") (pinfunction "6_6") (pintype "passive"))
      (node (ref "U13") (pin "B11") (pinfunction "TRST#_B11") (pintype "input"))
    )
    (net (code "77") (name "1V2") (class "Default")
      (node (ref "C68") (pin "2") (pintype "passive"))
      (node (ref "C69") (pin "2") (pintype "passive"))
      (node (ref "C70") (pin "2") (pintype "passive"))
      (node (ref "C71") (pin "2") (pintype "passive"))
      (node (ref "C72") (pin "2") (pintype "passive"))
      (node (ref "C73") (pin "2") (pintype "passive"))
      (node (ref "C74") (pin "2") (pintype "passive"))
      (node (ref "C75") (pin "2") (pintype "passive"))
      (node (ref "FB5") (pin "1") (pinfunction "1_1") (pintype "passive"))
      (node (ref "FB6") (pin "1") (pinfunction "1_1") (pintype "passive"))
      (node (ref "FB7") (pin "1") (pinfunction "1_1") (pintype "passive"))
      (node (ref "U13") (pin "B10") (pinfunction "VDD_B10") (pintype "power_in"))
      (node (ref "U13") (pin "C3") (pinfunction "VDD_C3") (pintype "power_in"))
      (node (ref "U13") (pin "E9") (pinfunction "VDD_E9") (pintype "power_in"))
      (node (ref "U13") (pin "F11") (pinfunction "VDD_F11") (pintype "power_in"))
      (node (ref "U13") (pin "H1") (pinfunction "VDD_H1") (pintype "power_in"))
      (node (ref "U13") (pin "J11") (pinfunction "VDD_J11") (pintype "power_in"))
      (node (ref "U13") (pin "L5") (pinfunction "VDD_L5") (pintype "power_in"))
      (node (ref "U13") (pin "L7") (pinfunction "VDD_L7") (pintype "power_in"))
    )
    (net (code "78") (name "1V8") (class "Default")
      (node (ref "C62") (pin "2") (pintype "passive"))
      (node (ref "C63") (pin "2") (pintype "passive"))
      (node (ref "C64") (pin "2") (pintype "passive"))
      (node (ref "C65") (pin "2") (pintype "passive"))
      (node (ref "C66") (pin "2") (pintype "passive"))
      (node (ref "C67") (pin "2") (pintype "passive"))
      (node (ref "FB4") (pin "1") (pinfunction "1_1") (pintype "passive"))
      (node (ref "R22") (pin "2") (pinfunction "2_2") (pintype "passive"))
      (node (ref "R23") (pin "2") (pinfunction "2_2") (pintype "passive"))
      (node (ref "R24") (pin "1") (pinfunction "1_1") (pintype "passive"))
      (node (ref "R25") (pin "2") (pinfunction "2_2") (pintype "passive"))
      (node (ref "R26") (pin "2") (pinfunction "2_2") (pintype "passive"))
      (node (ref "R27") (pin "2") (pinfunction "2_2") (pintype "passive"))
      (node (ref "U13") (pin "B1") (pinfunction "VIO4_B1") (pintype "power_in"))
      (node (ref "U13") (pin "C11") (pinfunction "VIO5_C11") (pintype "power_in"))
      (node (ref "U13") (pin "E3") (pinfunction "VIO3_E3") (pintype "power_in"))
      (node (ref "U13") (pin "F1") (pinfunction "VIO2_F1") (pintype "power_in"))
      (node (ref "U13") (pin "H11") (pinfunction "VIO1_H11") (pintype "power_in"))
      (node (ref "U13") (pin "L9") (pinfunction "VIO1_L9") (pintype "power_in"))
      (node (ref "U16") (pin "8") (pinfunction "VCC_8") (pintype "power_in"))
    )
    (net (code "79") (name "GND") (class "Default")
      (node (ref "C60") (pin "1") (pintype "passive"))
      (node (ref "C61") (pin "1") (pintype "passive"))
      (node (ref "C62") (pin "1") (pintype "passive"))
      (node (ref "C63") (pin "1") (pintype "passive"))
      (node (ref "C64") (pin "1") (pintype "passive"))
      (node (ref "C65") (pin "1") (pintype "passive"))
      (node (ref "C66") (pin "1") (pintype "passive"))
      (node (ref "C67") (pin "1") (pintype "passive"))
      (node (ref "C68") (pin "1") (pintype "passive"))
      (node (ref "C69") (pin "1") (pintype "passive"))
      (node (ref "C70") (pin "1") (pintype "passive"))
      (node (ref "C71") (pin "1") (pintype "passive"))
      (node (ref "C72") (pin "1") (pintype "passive"))
      (node (ref "C73") (pin "1") (pintype "passive"))
      (node (ref "C74") (pin "1") (pintype "passive"))
      (node (ref "C75") (pin "1") (pintype "passive"))
      (node (ref "C76") (pin "1") (pintype "passive"))
      (node (ref "C77") (pin "1") (pintype "passive"))
      (node (ref "C78") (pin "1") (pintype "passive"))
      (node (ref "C79") (pin "1") (pintype "passive"))
      (node (ref "C80") (pin "1") (pintype "passive"))
      (node (ref "C81") (pin "1") (pintype "passive"))
      (node (ref "C91") (pin "1") (pintype "passive"))
      (node (ref "C92") (pin "2") (pintype "passive"))
      (node (ref "C93") (pin "2") (pintype "passive"))
      (node (ref "J2") (pin "0") (pinfunction "Shield_0") (pintype "power_in"))
      (node (ref "J2") (pin "A1") (pinfunction "GND_A1") (pintype "power_in"))
      (node (ref "J2") (pin "A12") (pinfunction "GND_A12") (pintype "power_in"))
      (node (ref "J2") (pin "B1") (pinfunction "GND_B1") (pintype "power_in"))
      (node (ref "J2") (pin "B12") (pinfunction "GND_B12") (pintype "power_in"))
      (node (ref "P2") (pin "1") (pinfunction "1_1") (pintype "passive"))
      (node (ref "P3") (pin "5") (pinfunction "5_5") (pintype "passive"))
      (node (ref "P3") (pin "6") (pinfunction "6_6") (pintype "passive"))
      (node (ref "P4") (pin "3") (pinfunction "3_3") (pintype "passive"))
      (node (ref "R16") (pin "2") (pinfunction "2_2") (pintype "passive"))
      (node (ref "R17") (pin "2") (pinfunction "2_2") (pintype "passive"))
      (node (ref "R19") (pin "2") (pinfunction "2_2") (pintype "passive"))
      (node (ref "R20") (pin "2") (pinfunction "2_2") (pintype "passive"))
      (node (ref "R21") (pin "2") (pinfunction "2_2") (pintype "passive"))
      (node (ref "R28") (pin "2") (pinfunction "2_2") (pintype "passive"))
      (node (ref "R41") (pin "2") (pinfunction "2_2") (pintype "passive"))
      (node (ref "U12") (pin "2") (pinfunction "GND_2") (pintype "power_in"))
      (node (ref "U12") (pin "3") (pinfunction "~{EN}_3") (pintype "power_in"))
      (node (ref "U13") (pin "A1") (pinfunction "U3VSSQ_A1") (pintype "power_in"))
      (node (ref "U13") (pin "A8") (pinfunction "VSS_A8") (pintype "power_in"))
      (node (ref "U13") (pin "B7") (pinfunction "AVSS_B7") (pintype "power_in"))
      (node (ref "U13") (pin "B8") (pinfunction "VSS_B8") (pintype "power_in"))
      (node (ref "U13") (pin "B9") (pinfunction "VSS_B9") (pintype "power_in"))
      (node (ref "U13") (pin "D8") (pinfunction "VSS_D8") (pintype "power_in"))
      (node (ref "U13") (pin "E2") (pinfunction "VSS_E2") (pintype "power_in"))
      (node (ref "U13") (pin "G1") (pinfunction "VSS_G1") (pintype "power_in"))
      (node (ref "U13") (pin "G11") (pinfunction "VSS_G11") (pintype "power_in"))
      (node (ref "U13") (pin "K3") (pinfunction "VSS_K3") (pintype "power_in"))
      (node (ref "U13") (pin "K4") (pinfunction "VSS_K4") (pintype "power_in"))
      (node (ref "U13") (pin "L1") (pinfunction "VSS_L1") (pintype "power_in"))
      (node (ref "U13") (pin "L11") (pinfunction "VSS_L11") (pintype "power_in"))
      (node (ref "U13") (pin "L2") (pinfunction "VSS_L2") (pintype "power_in"))
      (node (ref "U13") (pin "L3") (pinfunction "VSS_L3") (pintype "power_in"))
      (node (ref "U13") (pin "L6") (pinfunction "VSS_L6") (pintype "power_in"))
      (node (ref "U14") (pin "3") (pinfunction "GND_3") (pintype "passive"))
      (node (ref "U14") (pin "8") (pinfunction "GND_8") (pintype "passive"))
      (node (ref "U15") (pin "3") (pinfunction "GND_3") (pintype "passive"))
      (node (ref "U15") (pin "8") (pinfunction "GND_8") (pintype "passive"))
      (node (ref "U16") (pin "3") (pinfunction "A2_3") (pintype "input"))
      (node (ref "U16") (pin "4") (pinfunction "GND_4") (pintype "power_in"))
      (node (ref "U16") (pin "7") (pinfunction "WP_7") (pintype "input"))
      (node (ref "U17") (pin "2") (pinfunction "GND_2") (pintype "power_in"))
      (node (ref "U18") (pin "3") (pinfunction "GND_3") (pintype "passive"))
      (node (ref "U18") (pin "8") (pinfunction "GND_8") (pintype "passive"))
    )
    (net (code "80") (name "LDO_3V3") (class "Default")
      (node (ref "C91") (pin "2") (pintype "passive"))
      (node (ref "U17") (pin "3") (pinfunction "Vcc_3") (pintype "power_in"))
    )
    (net (code "81") (name "Net-(J2-CC1)") (class "Default")
      (node (ref "J2") (pin "A5") (pinfunction "CC1_A5") (pintype "power_in"))
      (node (ref "R17") (pin "1") (pinfunction "1_1") (pintype "passive"))
    )
    (net (code "82") (name "Net-(J2-CC2)") (class "Default")
      (node (ref "J2") (pin "B5") (pinfunction "CC2_B5") (pintype "power_in"))
      (node (ref "R16") (pin "1") (pinfunction "1_1") (pintype "passive"))
    )
    (net (code "83") (name "Net-(LED1-PadK)") (class "Default")
      (node (ref "LED1") (pin "K") (pinfunction "K_K") (pintype "passive"))
      (node (ref "R41") (pin "1") (pinfunction "1_1") (pintype "passive"))
    )
    (net (code "84") (name "Net-(U13B-FSLC[0])") (class "Default")
      (node (ref "R21") (pin "1") (pinfunction "1_1") (pintype "passive"))
      (node (ref "U13") (pin "B2") (pinfunction "FSLC[0]_B2") (pintype "input"))
      (node (ref "U13") (pin "B4") (pinfunction "FSLC[1]_B4") (pintype "input"))
      (node (ref "U13") (pin "E6") (pinfunction "FSLC[2]_E6") (pintype "input"))
    )
    (net (code "85") (name "Net-(U13B-RESET#)") (class "Default")
      (node (ref "R22") (pin "1") (pinfunction "1_1") (pintype "passive"))
      (node (ref "U13") (pin "C5") (pinfunction "RESET#_C5") (pintype "input"))
    )
    (net (code "86") (name "Net-(U13B-R_USB2)") (class "Default")
      (node (ref "R19") (pin "1") (pinfunction "1_1") (pintype "passive"))
      (node (ref "U13") (pin "C8") (pinfunction "R_USB2_C8") (pintype "passive"))
    )
    (net (code "87") (name "Net-(U13B-R_USB3)") (class "Default")
      (node (ref "R20") (pin "1") (pinfunction "1_1") (pintype "passive"))
      (node (ref "U13") (pin "B3") (pinfunction "R_USB3_B3") (pintype "passive"))
    )
    (net (code "88") (name "Net-(U13B-XTALIN)") (class "Default")
      (node (ref "C78") (pin "2") (pintype "passive"))
      (node (ref "U13") (pin "C6") (pinfunction "XTALIN_C6") (pintype "passive"))
      (node (ref "X2") (pin "1") (pinfunction "X1_1") (pintype "passive"))
    )
    (net (code "89") (name "Net-(U13B-XTALOUT)") (class "Default")
      (node (ref "C79") (pin "2") (pintype "passive"))
      (node (ref "U13") (pin "C7") (pinfunction "XTALOUT_C7") (pintype "passive"))
      (node (ref "X2") (pin "3") (pinfunction "X2_3") (pintype "passive"))
    )
    (net (code "90") (name "Net-(U13C-AVDD)") (class "Default")
      (node (ref "C76") (pin "2") (pintype "passive"))
      (node (ref "C77") (pin "2") (pintype "passive"))
      (node (ref "FB5") (pin "2") (pinfunction "2_2") (pintype "passive"))
      (node (ref "U13") (pin "A7") (pinfunction "AVDD_A7") (pintype "power_in"))
    )
    (net (code "91") (name "Net-(U13C-CVDDQ)") (class "Default")
      (node (ref "C60") (pin "2") (pintype "passive"))
      (node (ref "C61") (pin "2") (pintype "passive"))
      (node (ref "FB4") (pin "2") (pinfunction "2_2") (pintype "passive"))
      (node (ref "U13") (pin "B6") (pinfunction "CVDDQ_B6") (pintype "power_in"))
    )
    (net (code "92") (name "Net-(U13C-U3RXVDDQ)") (class "Default")
      (node (ref "C81") (pin "2") (pintype "passive"))
      (node (ref "C93") (pin "1") (pintype "passive"))
      (node (ref "FB7") (pin "2") (pinfunction "2_2") (pintype "passive"))
      (node (ref "U13") (pin "A2") (pinfunction "U3RXVDDQ_A2") (pintype "power_in"))
    )
    (net (code "93") (name "Net-(U13C-U3TXVDDQ)") (class "Default")
      (node (ref "C80") (pin "2") (pintype "passive"))
      (node (ref "C92") (pin "1") (pintype "passive"))
      (node (ref "FB6") (pin "2") (pinfunction "2_2") (pintype "passive"))
      (node (ref "U13") (pin "B5") (pinfunction "U3TXVDDQ_B5") (pintype "power_in"))
    )
    (net (code "94") (name "VUSB") (class "Default")
      (node (ref "J2") (pin "A4") (pinfunction "VBUS_A4") (pintype "power_in"))
      (node (ref "J2") (pin "A9") (pinfunction "VBUS_A9") (pintype "power_in"))
      (node (ref "J2") (pin "B4") (pinfunction "VBUS_B4") (pintype "power_in"))
      (node (ref "J2") (pin "B9") (pinfunction "VBUS_B9") (pintype "power_in"))
      (node (ref "U12") (pin "1") (pinfunction "IN_1") (pintype "power_in"))
    )
    (net (code "95") (name "unconnected-(J2-SBU1-PadA8)") (class "Default")
      (node (ref "J2") (pin "A8") (pinfunction "SBU1_A8") (pintype "power_in"))
    )
    (net (code "96") (name "unconnected-(J2-SBU2-PadB8)") (class "Default")
      (node (ref "J2") (pin "B8") (pinfunction "SBU2_B8") (pintype "power_in"))
    )
    (net (code "97") (name "unconnected-(U12-FLAG-Pad4)") (class "Default")
      (node (ref "U12") (pin "4") (pinfunction "FLAG_4") (pintype "power_in"))
    )
    (net (code "98") (name "unconnected-(U13A-GPIO[18]-PadK7)") (class "Default")
      (node (ref "U13") (pin "K7") (pinfunction "GPIO[18]_K7") (pintype "bidirectional"))
    )
    (net (code "99") (name "unconnected-(U13A-GPIO[20]-PadH7)") (class "Default")
      (node (ref "U13") (pin "H7") (pinfunction "GPIO[20]_H7") (pintype "bidirectional"))
    )
    (net (code "100") (name "unconnected-(U13A-GPIO[23]-PadK6)") (class "Default")
      (node (ref "U13") (pin "K6") (pinfunction "GPIO[23]_K6") (pintype "bidirectional"))
    )
    (net (code "101") (name "unconnected-(U13A-GPIO[25]-PadG5)") (class "Default")
      (node (ref "U13") (pin "G5") (pinfunction "GPIO[25]_G5") (pintype "bidirectional"))
    )
    (net (code "102") (name "unconnected-(U13A-GPIO[27]-PadK5)") (class "Default")
      (node (ref "U13") (pin "K5") (pinfunction "GPIO[27]_K5") (pintype "bidirectional"))
    )
    (net (code "103") (name "unconnected-(U13A-GPIO[28]-PadJ5)") (class "Default")
      (node (ref "U13") (pin "J5") (pinfunction "GPIO[28]_J5") (pintype "bidirectional"))
    )
    (net (code "104") (name "unconnected-(U13A-GPIO[29]-PadH5)") (class "Default")
      (node (ref "U13") (pin "H5") (pinfunction "GPIO[29]_H5") (pintype "bidirectional"))
    )
    (net (code "105") (name "unconnected-(U13A-GPIO[45]-PadF2)") (class "Default")
      (node (ref "U13") (pin "F2") (pinfunction "GPIO[45]_F2") (pintype "bidirectional"))
    )
    (net (code "106") (name "unconnected-(U13A-GPIO[51]-PadD2)") (class "Default")
      (node (ref "U13") (pin "D2") (pinfunction "GPIO[51]_D2") (pintype "bidirectional"))
    )
    (net (code "107") (name "unconnected-(U13A-GPIO[53]-PadD4)") (class "Default")
      (node (ref "U13") (pin "D4") (pinfunction "GPIO[53]_D4") (pintype "bidirectional"))
    )
    (net (code "108") (name "unconnected-(U13A-GPIO[57]-PadC4)") (class "Default")
      (node (ref "U13") (pin "C4") (pinfunction "GPIO[57]_C4") (pintype "bidirectional"))
    )
    (net (code "109") (name "unconnected-(U13A-O[60]-PadD11)") (class "Default")
      (node (ref "U13") (pin "D11") (pinfunction "O[60]_D11") (pintype "output"))
    )
    (net (code "110") (name "unconnected-(U13B-CLKIN-PadD7)") (class "Default")
      (node (ref "U13") (pin "D7") (pinfunction "CLKIN_D7") (pintype "input"))
    )
    (net (code "111") (name "unconnected-(U13B-CLKIN_32-PadD6)") (class "Default")
      (node (ref "U13") (pin "D6") (pinfunction "CLKIN_32_D6") (pintype "input"))
    )
    (net (code "112") (name "unconnected-(U13B-INT#-PadL8)") (class "Default")
      (node (ref "U13") (pin "L8") (pinfunction "INT#_L8") (pintype "bidirectional"))
    )
    (net (code "113") (name "unconnected-(U13B-NC-PadA11)") (class "Default")
      (node (ref "U13") (pin "A11") (pinfunction "NC_A11") (pintype "passive"))
    )
    (net (code "114") (name "unconnected-(U13B-OTG_ID-PadC9)") (class "Default")
      (node (ref "U13") (pin "C9") (pinfunction "OTG_ID_C9") (pintype "input"))
    )
    (net (code "115") (name "unconnected-(U13B-VBATT-PadE10)") (class "Default")
      (node (ref "U13") (pin "E10") (pinfunction "VBATT_E10") (pintype "power_in"))
    )
    (net (code "116") (name "unconnected-(U18-Pad4)") (class "Default")
      (node (ref "U18") (pin "4") (pintype "passive"))
    )
    (net (code "117") (name "unconnected-(U18-Pad5)") (class "Default")
      (node (ref "U18") (pin "5") (pintype "passive"))
    )
    (net (code "118") (name "unconnected-(U18-Pad6)") (class "Default")
      (node (ref "U18") (pin "6") (pintype "passive"))
    )
    (net (code "119") (name "unconnected-(U18-Pad7)") (class "Default")
      (node (ref "U18") (pin "7") (pintype "passive"))
    )
    (net (code "120") (name "unconnected-(X2-NC-Pad2)") (class "Default")
      (node (ref "X2") (pin "2") (pinfunction "NC_2") (pintype "passive"))
    )
    (net (code "121") (name "unconnected-(X2-NC-Pad4)") (class "Default")
      (node (ref "X2") (pin "4") (pinfunction "NC_4") (pintype "passive"))
    )
  )
)
